# CordobejroSch.net
KiCad netlist of a schematic drawn in Altium Designer
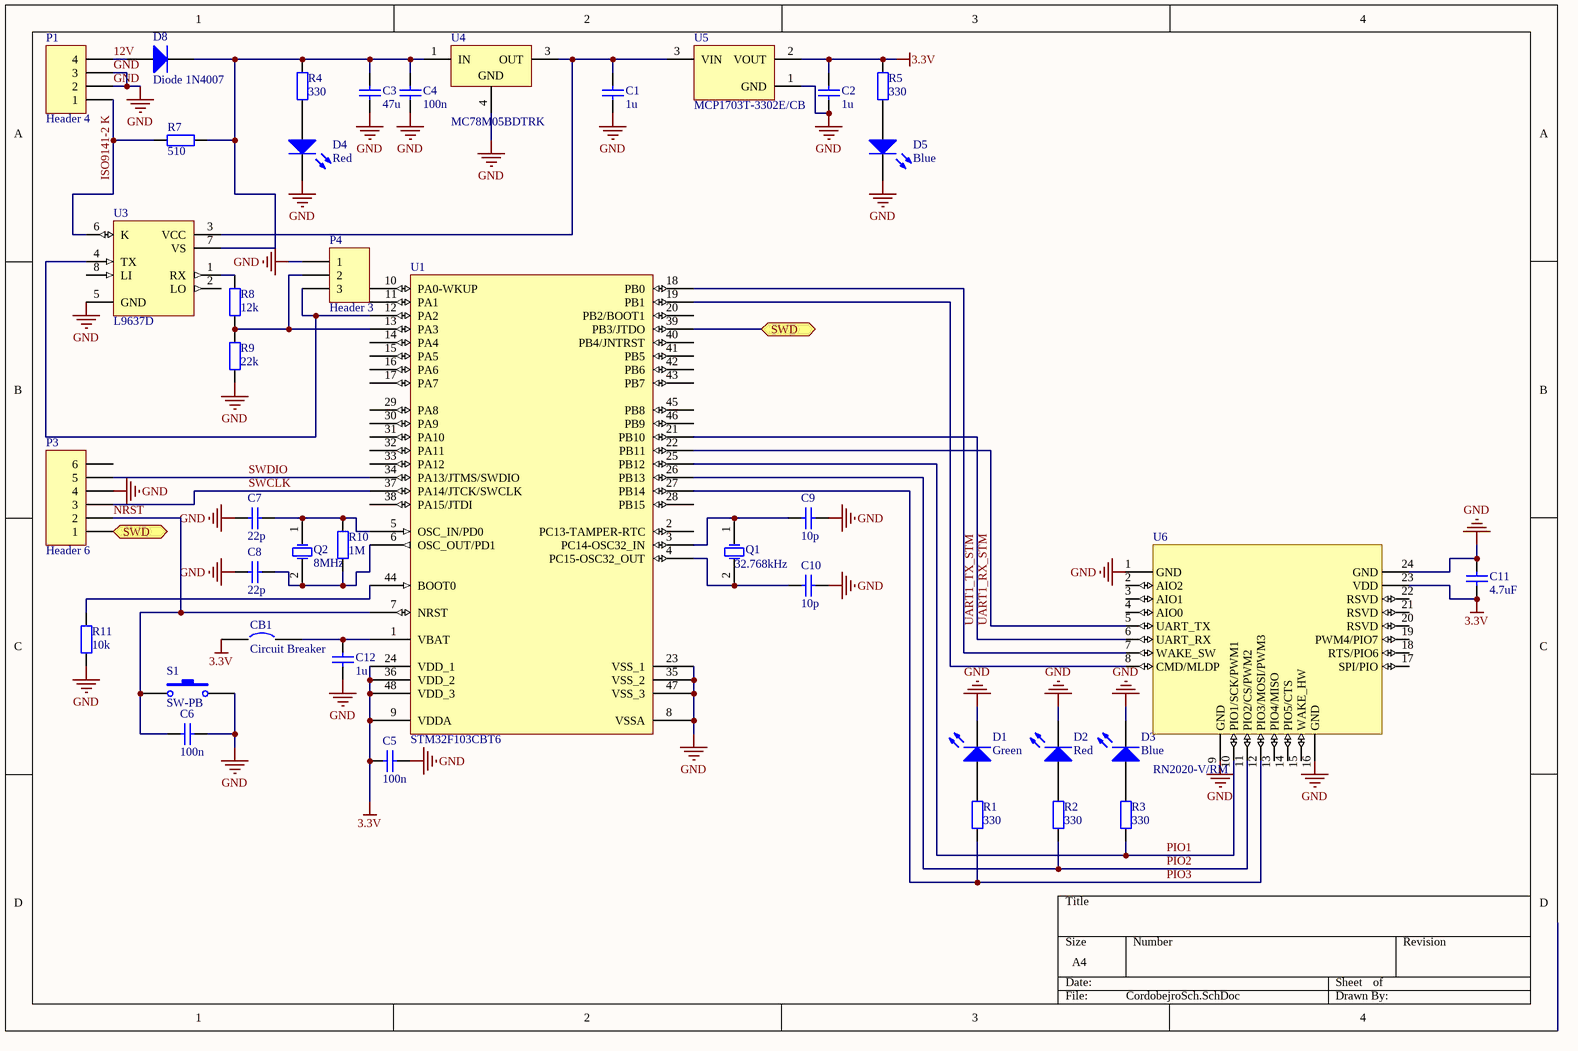
[diagram p0: CordobejroSch.SchDoc]

(export (version "E")
  (design (tool "Eeschema 10.0.6"))
  (components
    (comp (ref "C1")
      (value "1u")
      (footprint "0402")
      (description "Capacitor")
      (fields (field (name "PUBLISHER") "Altium Limited"))
      (libsource (lib "Miscellaneous Devices") (part "Cap"))
    )
    (comp (ref "C2")
      (value "1u")
      (footprint "0402")
      (description "Capacitor")
      (fields (field (name "PUBLISHER") "Altium Limited"))
      (libsource (lib "Miscellaneous Devices") (part "Cap"))
    )
    (comp (ref "C3")
      (value "47u")
      (footprint "0402")
      (description "Capacitor")
      (fields (field (name "PUBLISHER") "Altium Limited"))
      (libsource (lib "Miscellaneous Devices") (part "Cap"))
    )
    (comp (ref "C4")
      (value "100n")
      (footprint "0402")
      (description "Capacitor")
      (fields (field (name "PUBLISHER") "Altium Limited"))
      (libsource (lib "Miscellaneous Devices") (part "Cap"))
    )
    (comp (ref "C5")
      (value "100n")
      (footprint "0402")
      (description "Capacitor")
      (fields (field (name "PUBLISHER") "Altium Limited"))
      (libsource (lib "Miscellaneous Devices") (part "Cap"))
    )
    (comp (ref "C6")
      (value "100n")
      (footprint "0402")
      (description "Capacitor")
      (fields (field (name "PUBLISHER") "Altium Limited"))
      (libsource (lib "Miscellaneous Devices") (part "Cap"))
    )
    (comp (ref "C7")
      (value "22p")
      (footprint "0402")
      (description "Capacitor")
      (fields (field (name "PUBLISHER") "Altium Limited"))
      (libsource (lib "Miscellaneous Devices") (part "Cap"))
    )
    (comp (ref "C8")
      (value "22p")
      (footprint "0402")
      (description "Capacitor")
      (fields (field (name "PUBLISHER") "Altium Limited"))
      (libsource (lib "Miscellaneous Devices") (part "Cap"))
    )
    (comp (ref "C9")
      (value "10p")
      (footprint "0402")
      (description "Capacitor")
      (fields (field (name "PUBLISHER") "Altium Limited"))
      (libsource (lib "Miscellaneous Devices") (part "Cap"))
    )
    (comp (ref "C10")
      (value "10p")
      (footprint "0402")
      (description "Capacitor")
      (fields (field (name "PUBLISHER") "Altium Limited"))
      (libsource (lib "Miscellaneous Devices") (part "Cap"))
    )
    (comp (ref "C11")
      (value "4.7uF")
      (footprint "0402")
      (description "Capacitor")
      (fields (field (name "PUBLISHER") "Altium Limited"))
      (libsource (lib "Miscellaneous Devices") (part "Cap"))
    )
    (comp (ref "C12")
      (value "1u")
      (footprint "0402")
      (description "Capacitor")
      (fields (field (name "PUBLISHER") "Altium Limited"))
      (libsource (lib "Miscellaneous Devices") (part "Cap"))
    )
    (comp (ref "CB1")
      (value "Circuit Breaker")
      (footprint "SPST-2")
      (fields (field (name "PUBLISHER") "Altium Limited"))
      (libsource (lib "Miscellaneous Devices") (part "Circuit Breaker"))
    )
    (comp (ref "D1")
      (value "Green")
      (footprint "3.5X2.8X1.9")
      (description "Typical BLUE SiC LED")
      (fields (field (name "PUBLISHER") "Altium Limited"))
      (libsource (lib "Miscellaneous Devices") (part "LED3"))
    )
    (comp (ref "D2")
      (value "Red")
      (footprint "3.5X2.8X1.9")
      (description "Typical BLUE SiC LED")
      (fields (field (name "PUBLISHER") "Altium Limited"))
      (libsource (lib "Miscellaneous Devices") (part "LED3"))
    )
    (comp (ref "D3")
      (value "Blue")
      (footprint "3.5X2.8X1.9")
      (description "Typical BLUE SiC LED")
      (fields (field (name "PUBLISHER") "Altium Limited"))
      (libsource (lib "Miscellaneous Devices") (part "LED3"))
    )
    (comp (ref "D4")
      (value "Red")
      (footprint "3.5X2.8X1.9")
      (description "Typical BLUE SiC LED")
      (fields (field (name "PUBLISHER") "Altium Limited"))
      (libsource (lib "Miscellaneous Devices") (part "LED3"))
    )
    (comp (ref "D5")
      (value "Blue")
      (footprint "3.5X2.8X1.9")
      (description "Typical BLUE SiC LED")
      (fields (field (name "PUBLISHER") "Altium Limited"))
      (libsource (lib "Miscellaneous Devices") (part "LED3"))
    )
    (comp (ref "D8")
      (value "Diode 1N4007")
      (footprint "DO-41")
      (description "1 Amp General Purpose Rectifier")
      (fields (field (name "PUBLISHER") "Altium Limited"))
      (libsource (lib "Miscellaneous Devices") (part "Diode 1N4007"))
    )
    (comp (ref "P1")
      (value "Header 4")
      (footprint "HDR1X4")
      (description "Header, 4-Pin")
      (fields (field (name "PUBLISHER") "Altium Limited"))
      (libsource (lib "Miscellaneous Connectors") (part "Header 4"))
    )
    (comp (ref "P3")
      (value "Header 6")
      (footprint "HDR1X6")
      (description "Header, 6-Pin")
      (fields (field (name "PUBLISHER") "Altium Limited"))
      (libsource (lib "Miscellaneous Connectors") (part "Header 6"))
    )
    (comp (ref "P4")
      (value "Header 3")
      (footprint "HDR1X3")
      (description "Header, 3-Pin")
      (fields (field (name "PUBLISHER") "Altium Limited"))
      (libsource (lib "Miscellaneous Connectors") (part "Header 3"))
    )
    (comp (ref "Q1")
      (value "32.768kHz")
      (footprint "R38")
      (description "Crystal Oscillator")
      (fields (field (name "PUBLISHER") "Altium Limited"))
      (libsource (lib "Miscellaneous Devices") (part "XTAL"))
    )
    (comp (ref "Q2")
      (value "8MHz")
      (footprint "R38")
      (description "Crystal Oscillator")
      (fields (field (name "PUBLISHER") "Altium Limited"))
      (libsource (lib "Miscellaneous Devices") (part "XTAL"))
    )
    (comp (ref "R1")
      (value "330")
      (footprint "J1-0603")
      (description "Resistor")
      (fields (field (name "PUBLISHER") "Altium Limited"))
      (libsource (lib "") (part "Res2_1"))
    )
    (comp (ref "R2")
      (value "330")
      (footprint "J1-0603")
      (description "Resistor")
      (fields (field (name "PUBLISHER") "Altium Limited"))
      (libsource (lib "") (part "Res2_1"))
    )
    (comp (ref "R3")
      (value "330")
      (footprint "J1-0603")
      (description "Resistor")
      (fields (field (name "PUBLISHER") "Altium Limited"))
      (libsource (lib "") (part "Res2_1"))
    )
    (comp (ref "R4")
      (value "330")
      (footprint "J1-0603")
      (description "Resistor")
      (fields (field (name "PUBLISHER") "Altium Limited"))
      (libsource (lib "Miscellaneous Devices") (part "Res2"))
    )
    (comp (ref "R5")
      (value "330")
      (footprint "J1-0603")
      (description "Resistor")
      (fields (field (name "PUBLISHER") "Altium Limited"))
      (libsource (lib "Miscellaneous Devices") (part "Res2"))
    )
    (comp (ref "R7")
      (value "510")
      (footprint "J1-0603")
      (description "Resistor")
      (fields (field (name "PUBLISHER") "Altium Limited"))
      (libsource (lib "") (part "Res2_2"))
    )
    (comp (ref "R8")
      (value "12k")
      (footprint "J1-0603")
      (description "Resistor")
      (fields (field (name "PUBLISHER") "Altium Limited"))
      (libsource (lib "Miscellaneous Devices") (part "Res2"))
    )
    (comp (ref "R9")
      (value "22k")
      (footprint "J1-0603")
      (description "Resistor")
      (fields (field (name "PUBLISHER") "Altium Limited"))
      (libsource (lib "Miscellaneous Devices") (part "Res2"))
    )
    (comp (ref "R10")
      (value "1M")
      (footprint "J1-0603")
      (description "Resistor")
      (fields (field (name "PUBLISHER") "Altium Limited"))
      (libsource (lib "Miscellaneous Devices") (part "Res2"))
    )
    (comp (ref "R11")
      (value "10k")
      (footprint "J1-0603")
      (description "Resistor")
      (fields (field (name "PUBLISHER") "Altium Limited"))
      (libsource (lib "") (part "Res2_1"))
    )
    (comp (ref "S1")
      (value "SW-PB")
      (footprint "SPST-2")
      (description "Switch")
      (fields (field (name "PUBLISHER") "Altium Limited"))
      (libsource (lib "Miscellaneous Devices") (part "SW-PB"))
    )
    (comp (ref "U1")
      (value "STM32F103CBT6")
      (footprint "LQFP48_N")
      (description "STM32 ARM-based 32-bit MCU with 128 Kbytes Flash, 48-pin LQFP, Industrial Temperature")
      (fields (field (name "PUBLISHER") "Altium Limited"))
      (libsource (lib "ST Microcontroller 32-Bit STM32") (part "STM32F103CBT6"))
    )
    (comp (ref "U3")
      (value "L9637D")
      (footprint "SO8_N")
      (description "ISO 9141 Interface")
      (fields (field (name "PUBLISHER") "Altium Limited"))
      (libsource (lib "ST Automotive Diagnostic Serial Link") (part "L9637D"))
    )
    (comp (ref "U4")
      (value "MC78M05BDTRK")
      (footprint "369A-13")
      (description "Three-Terminal Medium Current Positive Voltage Regulator")
      (fields (field (name "PUBLISHER") "Altium Limited"))
      (libsource (lib "ON Semi Power Mgt Voltage Regulator") (part "MC78M05BDTRK"))
    )
    (comp (ref "U5")
      (value "MCP1703T-3302E/CB")
      (footprint "SOT-23A-CB3_N")
      (fields (field (name "PUBLISHER") "Altium Limited"))
      (libsource (lib "Microchip Power Mgt Line Regulator") (part "MCP1703T-3302E/CB"))
    )
    (comp (ref "U6")
      (value "RN2020-V/RM")
      (footprint "RN4020_ALT")
      (description "Microchip RN4020 Bluetooth")
      (libsource (lib "MicrochipTechnology") (part "RN2020-V/RM123"))
    )
  )
  (nets
    (net (code "1") (name "/12V") (class "Default")
      (node (ref "D8") (pin "1") (pinfunction "A_1") (pintype "passive"))
      (node (ref "P1") (pin "4") (pinfunction "4_4") (pintype "passive"))
    )
    (net (code "2") (name "/ISO9141-2 K") (class "Default")
      (node (ref "P1") (pin "1") (pinfunction "1_1") (pintype "passive"))
      (node (ref "R7") (pin "2") (pinfunction "2_2") (pintype "passive"))
      (node (ref "U3") (pin "6") (pinfunction "K_6") (pintype "bidirectional"))
    )
    (net (code "3") (name "/NRST") (class "Default")
      (node (ref "C6") (pin "2") (pinfunction "2_2") (pintype "passive"))
      (node (ref "P3") (pin "2") (pinfunction "2_2") (pintype "passive"))
      (node (ref "S1") (pin "1") (pinfunction "1_1") (pintype "passive"))
      (node (ref "U1") (pin "7") (pinfunction "NRST_7") (pintype "bidirectional"))
    )
    (net (code "4") (name "/PIO1") (class "Default")
      (node (ref "R3") (pin "2") (pinfunction "2_2") (pintype "passive"))
      (node (ref "U1") (pin "25") (pinfunction "PB12_25") (pintype "bidirectional"))
      (node (ref "U6") (pin "10") (pinfunction "PIO1/SCK/PWM1_10") (pintype "bidirectional"))
    )
    (net (code "5") (name "/PIO2") (class "Default")
      (node (ref "R2") (pin "2") (pinfunction "2_2") (pintype "passive"))
      (node (ref "U1") (pin "26") (pinfunction "PB13_26") (pintype "bidirectional"))
      (node (ref "U6") (pin "11") (pinfunction "PIO2/CS/PWM2_11") (pintype "bidirectional"))
    )
    (net (code "6") (name "/PIO3") (class "Default")
      (node (ref "R1") (pin "2") (pinfunction "2_2") (pintype "passive"))
      (node (ref "U1") (pin "27") (pinfunction "PB14_27") (pintype "bidirectional"))
      (node (ref "U6") (pin "12") (pinfunction "PIO3/MOSI/PWM3_12") (pintype "bidirectional"))
    )
    (net (code "7") (name "/SWCLK") (class "Default")
      (node (ref "P3") (pin "3") (pinfunction "3_3") (pintype "passive"))
      (node (ref "U1") (pin "37") (pinfunction "PA14/JTCK/SWCLK_37") (pintype "bidirectional"))
    )
    (net (code "8") (name "/SWD") (class "Default")
      (node (ref "P3") (pin "1") (pinfunction "1_1") (pintype "passive"))
      (node (ref "U1") (pin "39") (pinfunction "PB3/JTDO_39") (pintype "bidirectional"))
    )
    (net (code "9") (name "/SWDIO") (class "Default")
      (node (ref "P3") (pin "5") (pinfunction "5_5") (pintype "passive"))
      (node (ref "U1") (pin "34") (pinfunction "PA13/JTMS/SWDIO_34") (pintype "bidirectional"))
    )
    (net (code "10") (name "/UART1_RX_STM") (class "Default")
      (node (ref "U1") (pin "22") (pinfunction "PB11_22") (pintype "bidirectional"))
      (node (ref "U6") (pin "5") (pinfunction "UART_TX_5") (pintype "bidirectional"))
    )
    (net (code "11") (name "/UART1_TX_STM") (class "Default")
      (node (ref "U1") (pin "21") (pinfunction "PB10_21") (pintype "bidirectional"))
      (node (ref "U6") (pin "6") (pinfunction "UART_RX_6") (pintype "bidirectional"))
    )
    (net (code "12") (name "3.3V") (class "Default")
      (node (ref "C11") (pin "1") (pinfunction "1_1") (pintype "passive"))
      (node (ref "C2") (pin "2") (pinfunction "2_2") (pintype "passive"))
      (node (ref "C5") (pin "2") (pinfunction "2_2") (pintype "passive"))
      (node (ref "CB1") (pin "1") (pinfunction "1_1") (pintype "passive"))
      (node (ref "R5") (pin "2") (pinfunction "2_2") (pintype "passive"))
      (node (ref "U1") (pin "24") (pinfunction "VDD_1_24") (pintype "power_in"))
      (node (ref "U1") (pin "36") (pinfunction "VDD_2_36") (pintype "power_in"))
      (node (ref "U1") (pin "48") (pinfunction "VDD_3_48") (pintype "power_in"))
      (node (ref "U1") (pin "9") (pinfunction "VDDA_9") (pintype "power_in"))
      (node (ref "U5") (pin "2") (pinfunction "VOUT_2") (pintype "power_in"))
      (node (ref "U6") (pin "23") (pinfunction "VDD_23") (pintype "power_in"))
    )
    (net (code "13") (name "GND") (class "Default")
      (node (ref "C1") (pin "1") (pinfunction "1_1") (pintype "passive"))
      (node (ref "C10") (pin "1") (pinfunction "1_1") (pintype "passive"))
      (node (ref "C11") (pin "2") (pinfunction "2_2") (pintype "passive"))
      (node (ref "C12") (pin "1") (pinfunction "1_1") (pintype "passive"))
      (node (ref "C2") (pin "1") (pinfunction "1_1") (pintype "passive"))
      (node (ref "C3") (pin "1") (pinfunction "1_1") (pintype "passive"))
      (node (ref "C4") (pin "1") (pinfunction "1_1") (pintype "passive"))
      (node (ref "C5") (pin "1") (pinfunction "1_1") (pintype "passive"))
      (node (ref "C6") (pin "1") (pinfunction "1_1") (pintype "passive"))
      (node (ref "C7") (pin "2") (pinfunction "2_2") (pintype "passive"))
      (node (ref "C8") (pin "2") (pinfunction "2_2") (pintype "passive"))
      (node (ref "C9") (pin "1") (pinfunction "1_1") (pintype "passive"))
      (node (ref "D1") (pin "2") (pinfunction "K_2") (pintype "passive"))
      (node (ref "D2") (pin "2") (pinfunction "K_2") (pintype "passive"))
      (node (ref "D3") (pin "2") (pinfunction "K_2") (pintype "passive"))
      (node (ref "D4") (pin "2") (pinfunction "K_2") (pintype "passive"))
      (node (ref "D5") (pin "2") (pinfunction "K_2") (pintype "passive"))
      (node (ref "P1") (pin "2") (pinfunction "2_2") (pintype "passive"))
      (node (ref "P1") (pin "3") (pinfunction "3_3") (pintype "passive"))
      (node (ref "P3") (pin "4") (pinfunction "4_4") (pintype "passive"))
      (node (ref "P4") (pin "1") (pinfunction "1_1") (pintype "passive"))
      (node (ref "R11") (pin "2") (pinfunction "2_2") (pintype "passive"))
      (node (ref "R9") (pin "1") (pinfunction "1_1") (pintype "passive"))
      (node (ref "S1") (pin "2") (pinfunction "2_2") (pintype "passive"))
      (node (ref "U1") (pin "23") (pinfunction "VSS_1_23") (pintype "power_in"))
      (node (ref "U1") (pin "35") (pinfunction "VSS_2_35") (pintype "power_in"))
      (node (ref "U1") (pin "47") (pinfunction "VSS_3_47") (pintype "power_in"))
      (node (ref "U1") (pin "8") (pinfunction "VSSA_8") (pintype "power_in"))
      (node (ref "U3") (pin "5") (pinfunction "GND_5") (pintype "power_in"))
      (node (ref "U4") (pin "4") (pinfunction "GND_4") (pintype "power_in"))
      (node (ref "U5") (pin "1") (pinfunction "GND_1") (pintype "power_in"))
      (node (ref "U6") (pin "1") (pinfunction "GND_1") (pintype "power_in"))
      (node (ref "U6") (pin "16") (pinfunction "GND_16") (pintype "power_in"))
      (node (ref "U6") (pin "24") (pinfunction "GND_24") (pintype "power_in"))
      (node (ref "U6") (pin "9") (pinfunction "GND_9") (pintype "power_in"))
    )
    (net (code "14") (name "Net-(D1-A)") (class "Default")
      (node (ref "D1") (pin "1") (pinfunction "A_1") (pintype "passive"))
      (node (ref "R1") (pin "1") (pinfunction "1_1") (pintype "passive"))
    )
    (net (code "15") (name "Net-(D2-A)") (class "Default")
      (node (ref "D2") (pin "1") (pinfunction "A_1") (pintype "passive"))
      (node (ref "R2") (pin "1") (pinfunction "1_1") (pintype "passive"))
    )
    (net (code "16") (name "Net-(D3-A)") (class "Default")
      (node (ref "D3") (pin "1") (pinfunction "A_1") (pintype "passive"))
      (node (ref "R3") (pin "1") (pinfunction "1_1") (pintype "passive"))
    )
    (net (code "17") (name "Net-(D4-A)") (class "Default")
      (node (ref "D4") (pin "1") (pinfunction "A_1") (pintype "passive"))
      (node (ref "R4") (pin "1") (pinfunction "1_1") (pintype "passive"))
    )
    (net (code "18") (name "Net-(D5-A)") (class "Default")
      (node (ref "D5") (pin "1") (pinfunction "A_1") (pintype "passive"))
      (node (ref "R5") (pin "1") (pinfunction "1_1") (pintype "passive"))
    )
    (net (code "19") (name "Net-(D8-K)") (class "Default")
      (node (ref "C3") (pin "2") (pinfunction "2_2") (pintype "passive"))
      (node (ref "C4") (pin "2") (pinfunction "2_2") (pintype "passive"))
      (node (ref "D8") (pin "2") (pinfunction "K_2") (pintype "passive"))
      (node (ref "R4") (pin "2") (pinfunction "2_2") (pintype "passive"))
      (node (ref "R7") (pin "1") (pinfunction "1_1") (pintype "passive"))
      (node (ref "U3") (pin "7") (pinfunction "VS_7") (pintype "power_in"))
      (node (ref "U4") (pin "1") (pinfunction "IN_1") (pintype "power_in"))
    )
    (net (code "20") (name "Net-(Q1-OSC1)") (class "Default")
      (node (ref "C9") (pin "2") (pinfunction "2_2") (pintype "passive"))
      (node (ref "Q1") (pin "1") (pinfunction "OSC1_1") (pintype "passive"))
      (node (ref "U1") (pin "3") (pinfunction "PC14-OSC32_IN_3") (pintype "bidirectional"))
    )
    (net (code "21") (name "Net-(Q1-OSC2)") (class "Default")
      (node (ref "C10") (pin "2") (pinfunction "2_2") (pintype "passive"))
      (node (ref "Q1") (pin "2") (pinfunction "OSC2_2") (pintype "passive"))
      (node (ref "U1") (pin "4") (pinfunction "PC15-OSC32_OUT_4") (pintype "bidirectional"))
    )
    (net (code "22") (name "Net-(Q2-OSC1)") (class "Default")
      (node (ref "C7") (pin "1") (pinfunction "1_1") (pintype "passive"))
      (node (ref "Q2") (pin "1") (pinfunction "OSC1_1") (pintype "passive"))
      (node (ref "R10") (pin "2") (pinfunction "2_2") (pintype "passive"))
      (node (ref "U1") (pin "5") (pinfunction "OSC_IN/PD0_5") (pintype "input"))
    )
    (net (code "23") (name "Net-(Q2-OSC2)") (class "Default")
      (node (ref "C8") (pin "1") (pinfunction "1_1") (pintype "passive"))
      (node (ref "Q2") (pin "2") (pinfunction "OSC2_2") (pintype "passive"))
      (node (ref "R10") (pin "1") (pinfunction "1_1") (pintype "passive"))
      (node (ref "U1") (pin "6") (pinfunction "OSC_OUT/PD1_6") (pintype "output"))
    )
    (net (code "24") (name "Net-(U1-BOOT0)") (class "Default")
      (node (ref "R11") (pin "1") (pinfunction "1_1") (pintype "passive"))
      (node (ref "U1") (pin "44") (pinfunction "BOOT0_44") (pintype "input"))
    )
    (net (code "25") (name "Net-(U1-PA2)") (class "Default")
      (node (ref "P4") (pin "3") (pinfunction "3_3") (pintype "passive"))
      (node (ref "U1") (pin "12") (pinfunction "PA2_12") (pintype "bidirectional"))
      (node (ref "U3") (pin "4") (pinfunction "TX_4") (pintype "input"))
    )
    (net (code "26") (name "Net-(U1-PA3)") (class "Default")
      (node (ref "P4") (pin "2") (pinfunction "2_2") (pintype "passive"))
      (node (ref "R8") (pin "1") (pinfunction "1_1") (pintype "passive"))
      (node (ref "R9") (pin "2") (pinfunction "2_2") (pintype "passive"))
      (node (ref "U1") (pin "13") (pinfunction "PA3_13") (pintype "bidirectional"))
    )
    (net (code "27") (name "Net-(U1-PB0)") (class "Default")
      (node (ref "U1") (pin "18") (pinfunction "PB0_18") (pintype "bidirectional"))
      (node (ref "U6") (pin "7") (pinfunction "WAKE_SW_7") (pintype "bidirectional"))
    )
    (net (code "28") (name "Net-(U1-PB1)") (class "Default")
      (node (ref "U1") (pin "19") (pinfunction "PB1_19") (pintype "bidirectional"))
      (node (ref "U6") (pin "8") (pinfunction "CMD/MLDP_8") (pintype "bidirectional"))
    )
    (net (code "29") (name "Net-(U1-VBAT)") (class "Default")
      (node (ref "C12") (pin "2") (pinfunction "2_2") (pintype "passive"))
      (node (ref "CB1") (pin "2") (pinfunction "2_2") (pintype "passive"))
      (node (ref "U1") (pin "1") (pinfunction "VBAT_1") (pintype "power_in"))
    )
    (net (code "30") (name "Net-(U3-RX)") (class "Default")
      (node (ref "R8") (pin "2") (pinfunction "2_2") (pintype "passive"))
      (node (ref "U3") (pin "1") (pinfunction "RX_1") (pintype "output"))
    )
    (net (code "31") (name "Net-(U3-VCC)") (class "Default")
      (node (ref "C1") (pin "2") (pinfunction "2_2") (pintype "passive"))
      (node (ref "U3") (pin "3") (pinfunction "VCC_3") (pintype "power_in"))
      (node (ref "U4") (pin "3") (pinfunction "OUT_3") (pintype "power_in"))
      (node (ref "U5") (pin "3") (pinfunction "VIN_3") (pintype "power_in"))
    )
    (net (code "32") (name "unconnected-(P3-Pad6)") (class "Default")
      (node (ref "P3") (pin "6") (pinfunction "6_6") (pintype "passive"))
    )
    (net (code "33") (name "unconnected-(U1-PA0-WKUP-Pad10)") (class "Default")
      (node (ref "U1") (pin "10") (pinfunction "PA0-WKUP_10") (pintype "bidirectional"))
    )
    (net (code "34") (name "unconnected-(U1-PA1-Pad11)") (class "Default")
      (node (ref "U1") (pin "11") (pinfunction "PA1_11") (pintype "bidirectional"))
    )
    (net (code "35") (name "unconnected-(U1-PA4-Pad14)") (class "Default")
      (node (ref "U1") (pin "14") (pinfunction "PA4_14") (pintype "bidirectional"))
    )
    (net (code "36") (name "unconnected-(U1-PA5-Pad15)") (class "Default")
      (node (ref "U1") (pin "15") (pinfunction "PA5_15") (pintype "bidirectional"))
    )
    (net (code "37") (name "unconnected-(U1-PA6-Pad16)") (class "Default")
      (node (ref "U1") (pin "16") (pinfunction "PA6_16") (pintype "bidirectional"))
    )
    (net (code "38") (name "unconnected-(U1-PA7-Pad17)") (class "Default")
      (node (ref "U1") (pin "17") (pinfunction "PA7_17") (pintype "bidirectional"))
    )
    (net (code "39") (name "unconnected-(U1-PA8-Pad29)") (class "Default")
      (node (ref "U1") (pin "29") (pinfunction "PA8_29") (pintype "bidirectional"))
    )
    (net (code "40") (name "unconnected-(U1-PA9-Pad30)") (class "Default")
      (node (ref "U1") (pin "30") (pinfunction "PA9_30") (pintype "bidirectional"))
    )
    (net (code "41") (name "unconnected-(U1-PA10-Pad31)") (class "Default")
      (node (ref "U1") (pin "31") (pinfunction "PA10_31") (pintype "bidirectional"))
    )
    (net (code "42") (name "unconnected-(U1-PA11-Pad32)") (class "Default")
      (node (ref "U1") (pin "32") (pinfunction "PA11_32") (pintype "bidirectional"))
    )
    (net (code "43") (name "unconnected-(U1-PA12-Pad33)") (class "Default")
      (node (ref "U1") (pin "33") (pinfunction "PA12_33") (pintype "bidirectional"))
    )
    (net (code "44") (name "unconnected-(U1-PA15{slash}JTDI-Pad38)") (class "Default")
      (node (ref "U1") (pin "38") (pinfunction "PA15/JTDI_38") (pintype "bidirectional"))
    )
    (net (code "45") (name "unconnected-(U1-PB2{slash}BOOT1-Pad20)") (class "Default")
      (node (ref "U1") (pin "20") (pinfunction "PB2/BOOT1_20") (pintype "bidirectional"))
    )
    (net (code "46") (name "unconnected-(U1-PB4{slash}JNTRST-Pad40)") (class "Default")
      (node (ref "U1") (pin "40") (pinfunction "PB4/JNTRST_40") (pintype "bidirectional"))
    )
    (net (code "47") (name "unconnected-(U1-PB5-Pad41)") (class "Default")
      (node (ref "U1") (pin "41") (pinfunction "PB5_41") (pintype "bidirectional"))
    )
    (net (code "48") (name "unconnected-(U1-PB6-Pad42)") (class "Default")
      (node (ref "U1") (pin "42") (pinfunction "PB6_42") (pintype "bidirectional"))
    )
    (net (code "49") (name "unconnected-(U1-PB7-Pad43)") (class "Default")
      (node (ref "U1") (pin "43") (pinfunction "PB7_43") (pintype "bidirectional"))
    )
    (net (code "50") (name "unconnected-(U1-PB8-Pad45)") (class "Default")
      (node (ref "U1") (pin "45") (pinfunction "PB8_45") (pintype "bidirectional"))
    )
    (net (code "51") (name "unconnected-(U1-PB9-Pad46)") (class "Default")
      (node (ref "U1") (pin "46") (pinfunction "PB9_46") (pintype "bidirectional"))
    )
    (net (code "52") (name "unconnected-(U1-PB15-Pad28)") (class "Default")
      (node (ref "U1") (pin "28") (pinfunction "PB15_28") (pintype "bidirectional"))
    )
    (net (code "53") (name "unconnected-(U1-PC13-TAMPER-RTC-Pad2)") (class "Default")
      (node (ref "U1") (pin "2") (pinfunction "PC13-TAMPER-RTC_2") (pintype "bidirectional"))
    )
    (net (code "54") (name "unconnected-(U3-LI-Pad8)") (class "Default")
      (node (ref "U3") (pin "8") (pinfunction "LI_8") (pintype "input"))
    )
    (net (code "55") (name "unconnected-(U3-LO-Pad2)") (class "Default")
      (node (ref "U3") (pin "2") (pinfunction "LO_2") (pintype "output"))
    )
    (net (code "56") (name "unconnected-(U6-AIO0-Pad4)") (class "Default")
      (node (ref "U6") (pin "4") (pinfunction "AIO0_4") (pintype "bidirectional"))
    )
    (net (code "57") (name "unconnected-(U6-AIO1-Pad3)") (class "Default")
      (node (ref "U6") (pin "3") (pinfunction "AIO1_3") (pintype "bidirectional"))
    )
    (net (code "58") (name "unconnected-(U6-AIO2-Pad2)") (class "Default")
      (node (ref "U6") (pin "2") (pinfunction "AIO2_2") (pintype "bidirectional"))
    )
    (net (code "59") (name "unconnected-(U6-PIO4{slash}MISO-Pad13)") (class "Default")
      (node (ref "U6") (pin "13") (pinfunction "PIO4/MISO_13") (pintype "bidirectional"))
    )
    (net (code "60") (name "unconnected-(U6-PIO5{slash}CTS-Pad14)") (class "Default")
      (node (ref "U6") (pin "14") (pinfunction "PIO5/CTS_14") (pintype "bidirectional"))
    )
    (net (code "61") (name "unconnected-(U6-PWM4{slash}PIO7-Pad19)") (class "Default")
      (node (ref "U6") (pin "19") (pinfunction "PWM4/PIO7_19") (pintype "bidirectional"))
    )
    (net (code "62") (name "unconnected-(U6-RSVD-Pad20)") (class "Default")
      (node (ref "U6") (pin "20") (pinfunction "RSVD_20") (pintype "bidirectional"))
    )
    (net (code "63") (name "unconnected-(U6-RSVD-Pad21)") (class "Default")
      (node (ref "U6") (pin "21") (pinfunction "RSVD_21") (pintype "bidirectional"))
    )
    (net (code "64") (name "unconnected-(U6-RSVD-Pad22)") (class "Default")
      (node (ref "U6") (pin "22") (pinfunction "RSVD_22") (pintype "bidirectional"))
    )
    (net (code "65") (name "unconnected-(U6-RTS{slash}PIO6-Pad18)") (class "Default")
      (node (ref "U6") (pin "18") (pinfunction "RTS/PIO6_18") (pintype "bidirectional"))
    )
    (net (code "66") (name "unconnected-(U6-SPI{slash}PIO-Pad17)") (class "Default")
      (node (ref "U6") (pin "17") (pinfunction "SPI/PIO_17") (pintype "bidirectional"))
    )
    (net (code "67") (name "unconnected-(U6-WAKE_HW-Pad15)") (class "Default")
      (node (ref "U6") (pin "15") (pinfunction "WAKE_HW_15") (pintype "bidirectional"))
    )
  )
)
